# I2CGPS.net
KiCad netlist of a schematic drawn in EAGLE
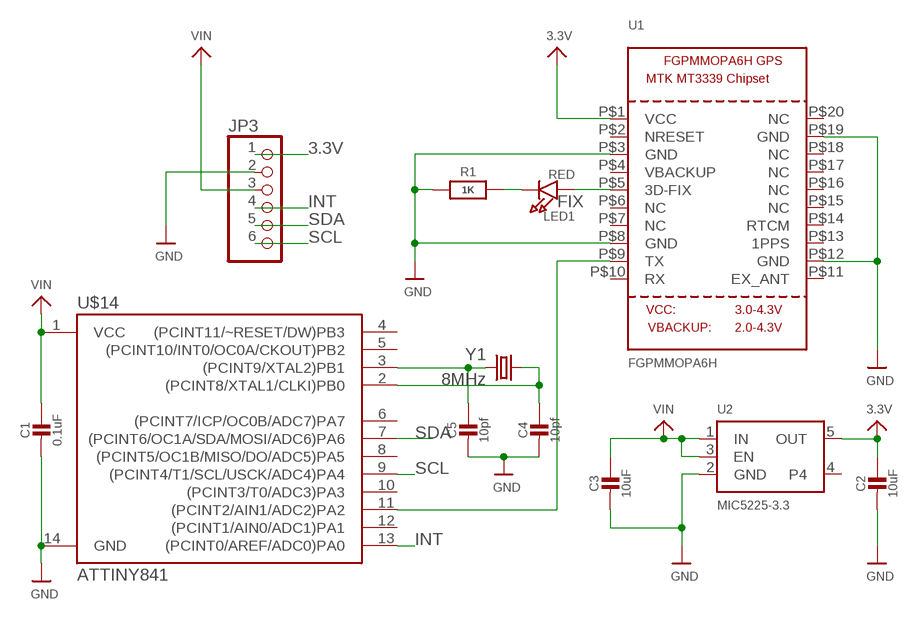
[diagram p0: schematic, sheet 1]

(export (version "E")
  (design (tool "Eeschema 10.0.6"))
  (components
    (comp (ref "C1")
      (value "0.1uF")
      (footprint "eagle-import:0805-NO")
      (libsource (lib "eagle-import") (part "CAP_CERAMIC0805-NOOUTLINE"))
    )
    (comp (ref "C2")
      (value "10uF")
      (footprint "eagle-import:0805-NO")
      (libsource (lib "eagle-import") (part "CAP_CERAMIC0805-NOOUTLINE"))
    )
    (comp (ref "C3")
      (value "10uF")
      (footprint "eagle-import:0805-NO")
      (libsource (lib "eagle-import") (part "CAP_CERAMIC0805-NOOUTLINE"))
    )
    (comp (ref "C4")
      (value "10pf")
      (footprint "eagle-import:0805-NO")
      (libsource (lib "eagle-import") (part "CAP_CERAMIC0805-NOOUTLINE"))
    )
    (comp (ref "C5")
      (value "10pf")
      (footprint "eagle-import:0805-NO")
      (libsource (lib "eagle-import") (part "CAP_CERAMIC0805-NOOUTLINE"))
    )
    (comp (ref "JP3")
      (value "PINHD-1X6CB")
      (footprint "eagle-import:1X06-CLEANBIG")
      (libsource (lib "eagle-import") (part "PINHD-1X6CB"))
    )
    (comp (ref "LED1")
      (value "RED")
      (footprint "eagle-import:CHIPLED_0805_NOOUTLINE")
      (libsource (lib "eagle-import") (part "LED0805_NOOUTLINE"))
    )
    (comp (ref "R1")
      (value "1K")
      (footprint "eagle-import:0805-NO")
      (libsource (lib "eagle-import") (part "RESISTOR0805_NOOUTLINE"))
    )
    (comp (ref "U$14")
      (value "ATTINY841")
      (footprint "eagle-import:SO14")
      (libsource (lib "eagle-import") (part "ATTINY84"))
    )
    (comp (ref "U1")
      (value "FGPMMOPA6H")
      (footprint "eagle-import:FGPMMOPA6H")
      (libsource (lib "eagle-import") (part "GPS_FGPMMOPA6H"))
    )
    (comp (ref "U2")
      (value "MIC5225-3.3")
      (footprint "eagle-import:SOT23-5")
      (libsource (lib "eagle-import") (part "VREG_SOT23-5"))
    )
    (comp (ref "Y1")
      (value "8MHz")
      (footprint "eagle-import:CRYSTAL-SMD-5X3")
      (libsource (lib "eagle-import") (part "CRYSTALCRYSTAL-SMD-5X3-12MHZ"))
    )
  )
  (nets
    (net (code "1") (name "/FIX") (class "Default")
      (node (ref "LED1") (pin "A") (pinfunction "A_A") (pintype "passive"))
      (node (ref "U1") (pin "P$5") (pinfunction "3D-FIX_P$5") (pintype "bidirectional"))
    )
    (net (code "2") (name "/INT") (class "Default")
      (node (ref "JP3") (pin "4") (pinfunction "4_4") (pintype "passive"))
      (node (ref "U$14") (pin "13") (pinfunction "(PCINT0/AREF/ADC0)PA0_13") (pintype "bidirectional"))
    )
    (net (code "3") (name "/SCL") (class "Default")
      (node (ref "JP3") (pin "6") (pinfunction "6_6") (pintype "passive"))
      (node (ref "U$14") (pin "9") (pinfunction "(PCINT4/T1/SCL/USCK/ADC4)PA4_9") (pintype "bidirectional"))
    )
    (net (code "4") (name "/SDA") (class "Default")
      (node (ref "JP3") (pin "5") (pinfunction "5_5") (pintype "passive"))
      (node (ref "U$14") (pin "7") (pinfunction "(PCINT6/OC1A/SDA/MOSI/ADC6)PA6_7") (pintype "bidirectional"))
    )
    (net (code "5") (name "3.3V") (class "Default")
      (node (ref "C2") (pin "1") (pinfunction "1_1") (pintype "passive"))
      (node (ref "JP3") (pin "1") (pinfunction "1_1") (pintype "passive"))
      (node (ref "U1") (pin "P$1") (pinfunction "VCC_P$1") (pintype "bidirectional"))
      (node (ref "U2") (pin "5") (pinfunction "OUT_5") (pintype "power_in"))
    )
    (net (code "6") (name "GND") (class "Default")
      (node (ref "C1") (pin "2") (pinfunction "2_2") (pintype "passive"))
      (node (ref "C2") (pin "2") (pinfunction "2_2") (pintype "passive"))
      (node (ref "C3") (pin "2") (pinfunction "2_2") (pintype "passive"))
      (node (ref "C4") (pin "2") (pinfunction "2_2") (pintype "passive"))
      (node (ref "C5") (pin "2") (pinfunction "2_2") (pintype "passive"))
      (node (ref "JP3") (pin "2") (pinfunction "2_2") (pintype "passive"))
      (node (ref "R1") (pin "1") (pinfunction "1_1") (pintype "passive"))
      (node (ref "U$14") (pin "14") (pinfunction "GND_14") (pintype "bidirectional"))
      (node (ref "U1") (pin "P$12") (pinfunction "GND_P$12") (pintype "bidirectional"))
      (node (ref "U1") (pin "P$19") (pinfunction "GND_P$19") (pintype "bidirectional"))
      (node (ref "U1") (pin "P$3") (pinfunction "GND_P$3") (pintype "bidirectional"))
      (node (ref "U1") (pin "P$8") (pinfunction "GND_P$8") (pintype "bidirectional"))
      (node (ref "U2") (pin "2") (pinfunction "GND_2") (pintype "power_in"))
    )
    (net (code "7") (name "Net-(LED1-PadC)") (class "Default")
      (node (ref "LED1") (pin "C") (pinfunction "C_C") (pintype "passive"))
      (node (ref "R1") (pin "2") (pinfunction "2_2") (pintype "passive"))
    )
    (net (code "8") (name "Net-(U$14-(PCINT2{slash}AIN1{slash}ADC2)PA2)") (class "Default")
      (node (ref "U$14") (pin "11") (pinfunction "(PCINT2/AIN1/ADC2)PA2_11") (pintype "bidirectional"))
      (node (ref "U1") (pin "P$9") (pinfunction "TX_P$9") (pintype "bidirectional"))
    )
    (net (code "9") (name "Net-(U$14-(PCINT8{slash}XTAL1{slash}CLKI)PB0)") (class "Default")
      (node (ref "C4") (pin "1") (pinfunction "1_1") (pintype "passive"))
      (node (ref "U$14") (pin "2") (pinfunction "(PCINT8/XTAL1/CLKI)PB0_2") (pintype "bidirectional"))
      (node (ref "Y1") (pin "1") (pinfunction "1_1") (pintype "passive"))
    )
    (net (code "10") (name "Net-(U$14-(PCINT9{slash}XTAL2)PB1)") (class "Default")
      (node (ref "C5") (pin "1") (pinfunction "1_1") (pintype "passive"))
      (node (ref "U$14") (pin "3") (pinfunction "(PCINT9/XTAL2)PB1_3") (pintype "bidirectional"))
      (node (ref "Y1") (pin "3") (pinfunction "2_3") (pintype "passive"))
    )
    (net (code "11") (name "VIN") (class "Default")
      (node (ref "C1") (pin "1") (pinfunction "1_1") (pintype "passive"))
      (node (ref "C3") (pin "1") (pinfunction "1_1") (pintype "passive"))
      (node (ref "JP3") (pin "3") (pinfunction "3_3") (pintype "passive"))
      (node (ref "U$14") (pin "1") (pinfunction "VCC_1") (pintype "bidirectional"))
      (node (ref "U2") (pin "1") (pinfunction "IN_1") (pintype "power_in"))
      (node (ref "U2") (pin "3") (pinfunction "EN_3") (pintype "input"))
    )
    (net (code "12") (name "unconnected-(U$14-(PCINT1{slash}AIN0{slash}ADC1)PA1-Pad12)") (class "Default")
      (node (ref "U$14") (pin "12") (pinfunction "(PCINT1/AIN0/ADC1)PA1_12") (pintype "bidirectional"))
    )
    (net (code "13") (name "unconnected-(U$14-(PCINT3{slash}T0{slash}ADC3)PA3-Pad10)") (class "Default")
      (node (ref "U$14") (pin "10") (pinfunction "(PCINT3/T0/ADC3)PA3_10") (pintype "bidirectional"))
    )
    (net (code "14") (name "unconnected-(U$14-(PCINT5{slash}OC1B{slash}MISO{slash}DO{slash}ADC5)PA5-Pad8)") (class "Default")
      (node (ref "U$14") (pin "8") (pinfunction "(PCINT5/OC1B/MISO/DO/ADC5)PA5_8") (pintype "bidirectional"))
    )
    (net (code "15") (name "unconnected-(U$14-(PCINT7{slash}ICP{slash}OC0B{slash}ADC7)PA7-Pad6)") (class "Default")
      (node (ref "U$14") (pin "6") (pinfunction "(PCINT7/ICP/OC0B/ADC7)PA7_6") (pintype "bidirectional"))
    )
    (net (code "16") (name "unconnected-(U$14-(PCINT10{slash}INT0{slash}OC0A{slash}CKOUT)PB2-Pad5)") (class "Default")
      (node (ref "U$14") (pin "5") (pinfunction "(PCINT10/INT0/OC0A/CKOUT)PB2_5") (pintype "bidirectional"))
    )
    (net (code "17") (name "unconnected-(U$14-(PCINT11{slash}~{RESET{slash}DW})PB3-Pad4)") (class "Default")
      (node (ref "U$14") (pin "4") (pinfunction "(PCINT11/~{RESET/DW})PB3_4") (pintype "bidirectional"))
    )
    (net (code "18") (name "unconnected-(U1-1PPS-PadP$13)") (class "Default")
      (node (ref "U1") (pin "P$13") (pinfunction "1PPS_P$13") (pintype "bidirectional"))
    )
    (net (code "19") (name "unconnected-(U1-EX_ANT-PadP$11)") (class "Default")
      (node (ref "U1") (pin "P$11") (pinfunction "EX_ANT_P$11") (pintype "bidirectional"))
    )
    (net (code "20") (name "unconnected-(U1-NC-PadP$6)") (class "Default")
      (node (ref "U1") (pin "P$6") (pinfunction "NC_P$6") (pintype "bidirectional"))
    )
    (net (code "21") (name "unconnected-(U1-NC-PadP$7)") (class "Default")
      (node (ref "U1") (pin "P$7") (pinfunction "NC_P$7") (pintype "bidirectional"))
    )
    (net (code "22") (name "unconnected-(U1-NC-PadP$15)") (class "Default")
      (node (ref "U1") (pin "P$15") (pinfunction "NC_P$15") (pintype "bidirectional"))
    )
    (net (code "23") (name "unconnected-(U1-NC-PadP$16)") (class "Default")
      (node (ref "U1") (pin "P$16") (pinfunction "NC_P$16") (pintype "bidirectional"))
    )
    (net (code "24") (name "unconnected-(U1-NC-PadP$17)") (class "Default")
      (node (ref "U1") (pin "P$17") (pinfunction "NC_P$17") (pintype "bidirectional"))
    )
    (net (code "25") (name "unconnected-(U1-NC-PadP$18)") (class "Default")
      (node (ref "U1") (pin "P$18") (pinfunction "NC_P$18") (pintype "bidirectional"))
    )
    (net (code "26") (name "unconnected-(U1-NC-PadP$20)") (class "Default")
      (node (ref "U1") (pin "P$20") (pinfunction "NC_P$20") (pintype "bidirectional"))
    )
    (net (code "27") (name "unconnected-(U1-NRESET-PadP$2)") (class "Default")
      (node (ref "U1") (pin "P$2") (pinfunction "NRESET_P$2") (pintype "bidirectional"))
    )
    (net (code "28") (name "unconnected-(U1-RTCM-PadP$14)") (class "Default")
      (node (ref "U1") (pin "P$14") (pinfunction "RTCM_P$14") (pintype "bidirectional"))
    )
    (net (code "29") (name "unconnected-(U1-RX-PadP$10)") (class "Default")
      (node (ref "U1") (pin "P$10") (pinfunction "RX_P$10") (pintype "bidirectional"))
    )
    (net (code "30") (name "unconnected-(U1-VBACKUP-PadP$4)") (class "Default")
      (node (ref "U1") (pin "P$4") (pinfunction "VBACKUP_P$4") (pintype "bidirectional"))
    )
    (net (code "31") (name "unconnected-(U2-P4-Pad4)") (class "Default")
      (node (ref "U2") (pin "4") (pinfunction "P4_4") (pintype "bidirectional"))
    )
  )
)
